# GLIDE.net
KiCad netlist of a schematic drawn in Altium Designer
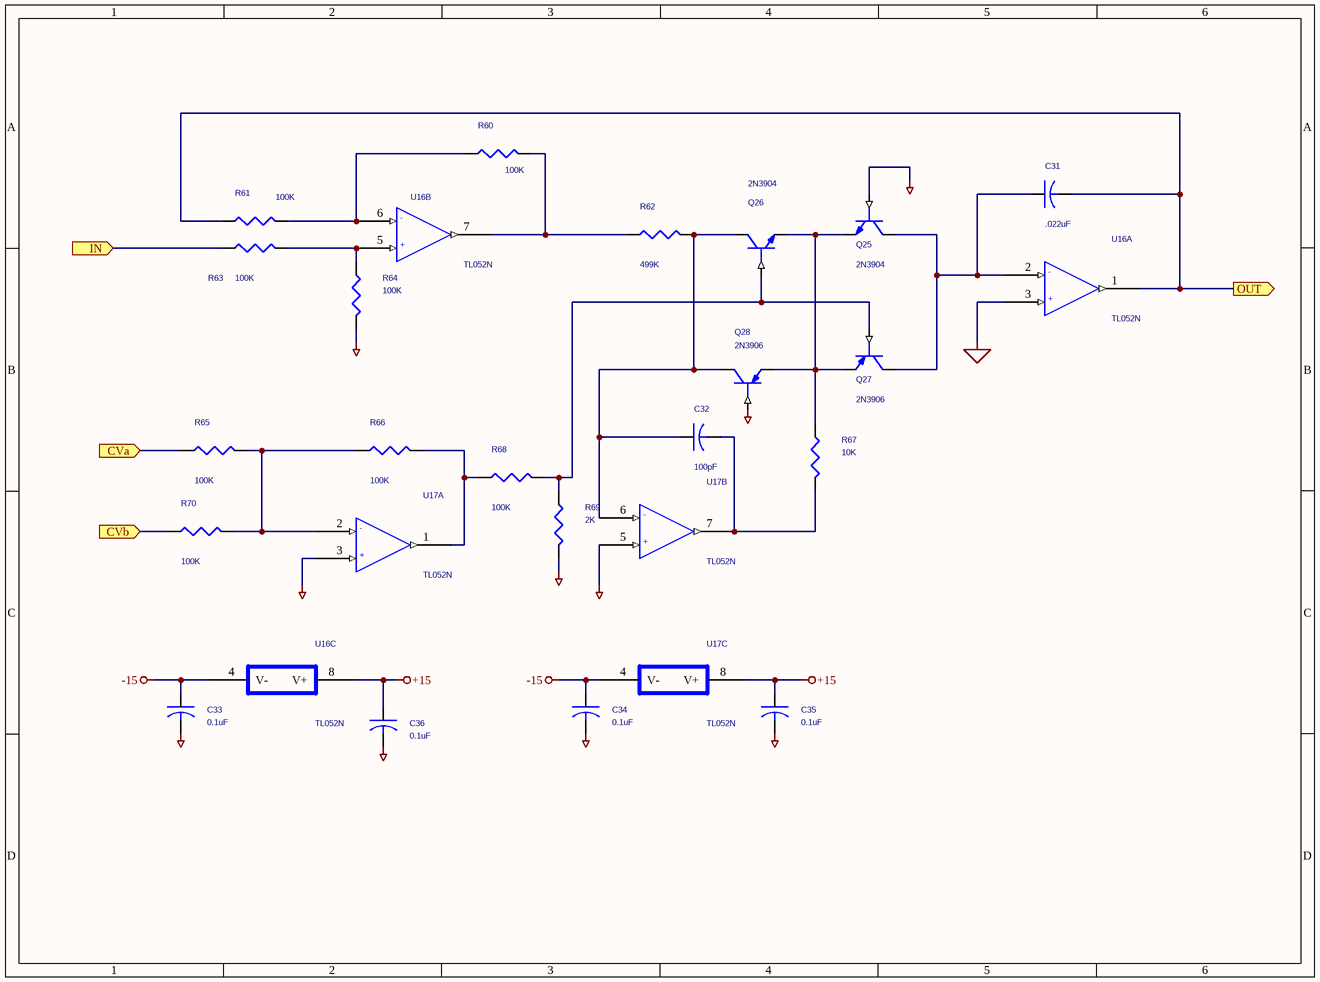
[diagram p0: GLIDE.SchDoc]

(export (version "E")
  (design (tool "Eeschema 10.0.6"))
  (components
    (comp (ref "C31") (value ".022uF") (libsource (lib "*") (part "CAP_Dup1")))
    (comp (ref "C32") (value "100pF") (libsource (lib "*") (part "CAP_Dup1")))
    (comp (ref "C33") (value "0.1uF") (libsource (lib "*") (part "CAP_Dup1")))
    (comp (ref "C34") (value "0.1uF") (libsource (lib "*") (part "CAP_Dup1")))
    (comp (ref "C35") (value "0.1uF") (libsource (lib "*") (part "CAP_Dup1")))
    (comp (ref "C36") (value "0.1uF") (libsource (lib "*") (part "CAP_Dup1")))
    (comp (ref "Q25") (value "2N3904") (footprint "TO92") (libsource (lib "*") (part "NPN")))
    (comp (ref "Q26") (value "2N3904") (footprint "TO92") (libsource (lib "*") (part "NPN")))
    (comp (ref "Q27") (value "2N3906") (footprint "TO92") (libsource (lib "*") (part "PNP")))
    (comp (ref "Q28") (value "2N3906") (footprint "TO92") (libsource (lib "*") (part "PNP")))
    (comp (ref "R60") (value "100K") (libsource (lib "*") (part "R_Dup1")))
    (comp (ref "R61") (value "100K") (libsource (lib "*") (part "R_Dup1")))
    (comp (ref "R62") (value "499K") (libsource (lib "*") (part "R_Dup1")))
    (comp (ref "R63") (value "100K") (libsource (lib "*") (part "R_Dup1")))
    (comp (ref "R64") (value "100K") (libsource (lib "*") (part "R_Dup1")))
    (comp (ref "R65") (value "100K") (libsource (lib "*") (part "R_Dup1")))
    (comp (ref "R66") (value "100K") (libsource (lib "*") (part "R_Dup1")))
    (comp (ref "R67") (value "10K") (libsource (lib "*") (part "R_Dup1")))
    (comp (ref "R68") (value "100K") (libsource (lib "*") (part "R_Dup1")))
    (comp (ref "R69") (value "2K") (libsource (lib "*") (part "R_Dup1")))
    (comp (ref "R70") (value "100K") (libsource (lib "*") (part "R_Dup1")))
    (comp (ref "U16") (value "TL052N") (footprint "DIP8") (libsource (lib "*") (part "TL052N")))
    (comp (ref "U17") (value "TL052N") (footprint "DIP8") (libsource (lib "*") (part "TL052N")))
  )
  (nets
    (net (code "1") (name "+15") (class "Default")
      (node (ref "C35") (pin "1") (pinfunction "1_1") (pintype "passive"))
      (node (ref "C36") (pin "1") (pinfunction "1_1") (pintype "passive"))
      (node (ref "U16") (pin "8") (pinfunction "V+_8") (pintype "passive"))
      (node (ref "U17") (pin "8") (pinfunction "V+_8") (pintype "passive"))
    )
    (net (code "2") (name "-15") (class "Default")
      (node (ref "C33") (pin "1") (pinfunction "1_1") (pintype "passive"))
      (node (ref "C34") (pin "1") (pinfunction "1_1") (pintype "passive"))
      (node (ref "U16") (pin "4") (pinfunction "V-_4") (pintype "passive"))
      (node (ref "U17") (pin "4") (pinfunction "V-_4") (pintype "passive"))
    )
    (net (code "3") (name "/CVa") (class "Default")
      (node (ref "R65") (pin "1") (pinfunction "1_1") (pintype "passive"))
    )
    (net (code "4") (name "/CVb") (class "Default")
      (node (ref "R70") (pin "1") (pinfunction "1_1") (pintype "passive"))
    )
    (net (code "5") (name "/IN") (class "Default")
      (node (ref "R63") (pin "1") (pinfunction "1_1") (pintype "passive"))
    )
    (net (code "6") (name "/OUT") (class "Default")
      (node (ref "C31") (pin "2") (pinfunction "2_2") (pintype "passive"))
      (node (ref "R61") (pin "1") (pinfunction "1_1") (pintype "passive"))
      (node (ref "U16") (pin "1") (pinfunction "OUT_1") (pintype "output"))
    )
    (net (code "7") (name "AGND") (class "Default")
      (node (ref "C33") (pin "2") (pinfunction "2_2") (pintype "passive"))
      (node (ref "C34") (pin "2") (pinfunction "2_2") (pintype "passive"))
      (node (ref "C35") (pin "2") (pinfunction "2_2") (pintype "passive"))
      (node (ref "C36") (pin "2") (pinfunction "2_2") (pintype "passive"))
      (node (ref "Q25") (pin "BASE") (pinfunction "BASE_BASE") (pintype "input"))
      (node (ref "Q28") (pin "BASE") (pinfunction "BASE_BASE") (pintype "input"))
      (node (ref "R64") (pin "2") (pinfunction "2_2") (pintype "passive"))
      (node (ref "R69") (pin "2") (pinfunction "2_2") (pintype "passive"))
      (node (ref "U17") (pin "3") (pinfunction "+_3") (pintype "input"))
      (node (ref "U17") (pin "5") (pinfunction "+_5") (pintype "input"))
    )
    (net (code "8") (name "GND_SIGNAL") (class "Default")
      (node (ref "U16") (pin "3") (pinfunction "+_3") (pintype "input"))
    )
    (net (code "9") (name "Net-(Q25-PadEMITTER)") (class "Default")
      (node (ref "Q25") (pin "EMITTER") (pinfunction "EMITTER_EMITTER") (pintype "passive"))
      (node (ref "Q26") (pin "EMITTER") (pinfunction "EMITTER_EMITTER") (pintype "passive"))
      (node (ref "Q27") (pin "EMITTER") (pinfunction "EMITTER_EMITTER") (pintype "passive"))
      (node (ref "Q28") (pin "EMITTER") (pinfunction "EMITTER_EMITTER") (pintype "passive"))
      (node (ref "R67") (pin "1") (pinfunction "1_1") (pintype "passive"))
    )
    (net (code "10") (name "Net-(Q26-PadBASE)") (class "Default")
      (node (ref "Q26") (pin "BASE") (pinfunction "BASE_BASE") (pintype "input"))
      (node (ref "Q27") (pin "BASE") (pinfunction "BASE_BASE") (pintype "input"))
      (node (ref "R68") (pin "2") (pinfunction "2_2") (pintype "passive"))
      (node (ref "R69") (pin "1") (pinfunction "1_1") (pintype "passive"))
    )
    (net (code "11") (name "Net-(U16A--)") (class "Default")
      (node (ref "C31") (pin "1") (pinfunction "1_1") (pintype "passive"))
      (node (ref "Q25") (pin "COLLECTOR") (pinfunction "COLLECTOR_COLLECTOR") (pintype "passive"))
      (node (ref "Q27") (pin "COLLECTOR") (pinfunction "COLLECTOR_COLLECTOR") (pintype "passive"))
      (node (ref "U16") (pin "2") (pinfunction "-_2") (pintype "input"))
    )
    (net (code "12") (name "Net-(U16B-+)") (class "Default")
      (node (ref "R63") (pin "2") (pinfunction "2_2") (pintype "passive"))
      (node (ref "R64") (pin "1") (pinfunction "1_1") (pintype "passive"))
      (node (ref "U16") (pin "5") (pinfunction "+_5") (pintype "input"))
    )
    (net (code "13") (name "Net-(U16B--)") (class "Default")
      (node (ref "R60") (pin "1") (pinfunction "1_1") (pintype "passive"))
      (node (ref "R61") (pin "2") (pinfunction "2_2") (pintype "passive"))
      (node (ref "U16") (pin "6") (pinfunction "-_6") (pintype "input"))
    )
    (net (code "14") (name "Net-(U16B-OUT)") (class "Default")
      (node (ref "R60") (pin "2") (pinfunction "2_2") (pintype "passive"))
      (node (ref "R62") (pin "1") (pinfunction "1_1") (pintype "passive"))
      (node (ref "U16") (pin "7") (pinfunction "OUT_7") (pintype "output"))
    )
    (net (code "15") (name "Net-(U17A--)") (class "Default")
      (node (ref "R65") (pin "2") (pinfunction "2_2") (pintype "passive"))
      (node (ref "R66") (pin "1") (pinfunction "1_1") (pintype "passive"))
      (node (ref "R70") (pin "2") (pinfunction "2_2") (pintype "passive"))
      (node (ref "U17") (pin "2") (pinfunction "-_2") (pintype "input"))
    )
    (net (code "16") (name "Net-(U17A-OUT)") (class "Default")
      (node (ref "R66") (pin "2") (pinfunction "2_2") (pintype "passive"))
      (node (ref "R68") (pin "1") (pinfunction "1_1") (pintype "passive"))
      (node (ref "U17") (pin "1") (pinfunction "OUT_1") (pintype "output"))
    )
    (net (code "17") (name "Net-(U17B--)") (class "Default")
      (node (ref "C32") (pin "1") (pinfunction "1_1") (pintype "passive"))
      (node (ref "Q26") (pin "COLLECTOR") (pinfunction "COLLECTOR_COLLECTOR") (pintype "passive"))
      (node (ref "Q28") (pin "COLLECTOR") (pinfunction "COLLECTOR_COLLECTOR") (pintype "passive"))
      (node (ref "R62") (pin "2") (pinfunction "2_2") (pintype "passive"))
      (node (ref "U17") (pin "6") (pinfunction "-_6") (pintype "input"))
    )
    (net (code "18") (name "Net-(U17B-OUT)") (class "Default")
      (node (ref "C32") (pin "2") (pinfunction "2_2") (pintype "passive"))
      (node (ref "R67") (pin "2") (pinfunction "2_2") (pintype "passive"))
      (node (ref "U17") (pin "7") (pinfunction "OUT_7") (pintype "output"))
    )
  )
)
